# Power_System.net
KiCad netlist of a schematic drawn in Altium Designer
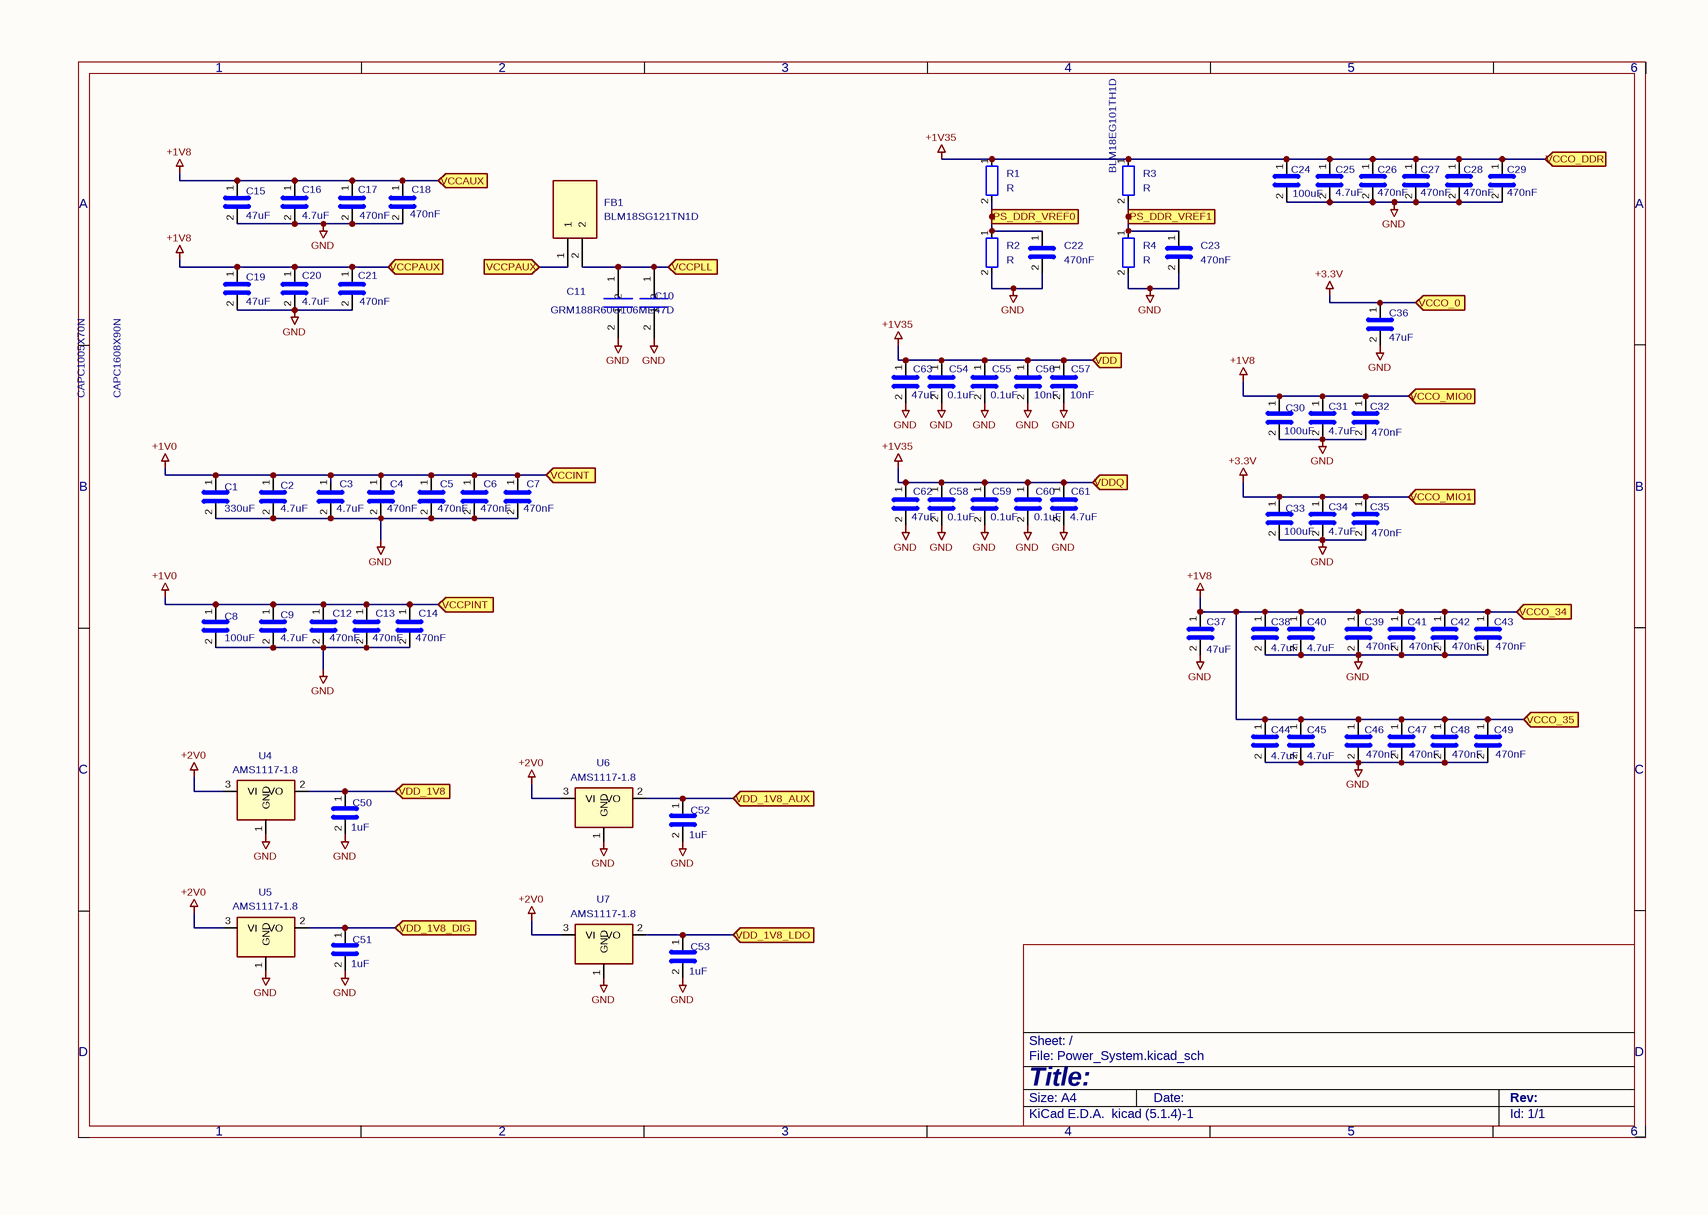
[diagram p0: Power_System.SchDoc]

(export (version "E")
  (design (tool "Eeschema 10.0.6"))
  (components
    (comp (ref "C1") (value "330uF") (libsource (lib "Device") (part "C")))
    (comp (ref "C2")
      (value "4.7uF")
      (footprint "C_0805_2012Metric_Pad1.18x1.45mm_HandSolder")
      (libsource (lib "Device") (part "C"))
    )
    (comp (ref "C3")
      (value "4.7uF")
      (footprint "C_0805_2012Metric_Pad1.18x1.45mm_HandSolder")
      (libsource (lib "Device") (part "C"))
    )
    (comp (ref "C4")
      (value "470nF")
      (footprint "C_0402_1005Metric_Pad0.74x0.62mm_HandSolder")
      (libsource (lib "Device") (part "C"))
    )
    (comp (ref "C5")
      (value "470nF")
      (footprint "C_0402_1005Metric_Pad0.74x0.62mm_HandSolder")
      (libsource (lib "Device") (part "C"))
    )
    (comp (ref "C6")
      (value "470nF")
      (footprint "C_0402_1005Metric_Pad0.74x0.62mm_HandSolder")
      (libsource (lib "Device") (part "C"))
    )
    (comp (ref "C7")
      (value "470nF")
      (footprint "C_0402_1005Metric_Pad0.74x0.62mm_HandSolder")
      (libsource (lib "Device") (part "C"))
    )
    (comp (ref "C8")
      (value "100uF")
      (footprint "C_0805_2012Metric_Pad1.18x1.45mm_HandSolder")
      (libsource (lib "Device") (part "C"))
    )
    (comp (ref "C9")
      (value "4.7uF")
      (footprint "C_0805_2012Metric_Pad1.18x1.45mm_HandSolder")
      (libsource (lib "Device") (part "C"))
    )
    (comp (ref "C10")
      (value "GRM188R60G106ME47D")
      (footprint "CAPC1608X90N")
      (libsource (lib "SamacSys") (part "GRM188R60G106ME47D"))
    )
    (comp (ref "C11")
      (value "GRM155R60J474KE19D")
      (footprint "CAPC1005X70N")
      (libsource (lib "SamacSys") (part "GRM155R60J474KE19D"))
    )
    (comp (ref "C12")
      (value "470nF")
      (footprint "C_0402_1005Metric_Pad0.74x0.62mm_HandSolder")
      (libsource (lib "Device") (part "C"))
    )
    (comp (ref "C13")
      (value "470nF")
      (footprint "C_0402_1005Metric_Pad0.74x0.62mm_HandSolder")
      (libsource (lib "Device") (part "C"))
    )
    (comp (ref "C14")
      (value "470nF")
      (footprint "C_0402_1005Metric_Pad0.74x0.62mm_HandSolder")
      (libsource (lib "Device") (part "C"))
    )
    (comp (ref "C15")
      (value "47uF")
      (footprint "C_0805_2012Metric_Pad1.18x1.45mm_HandSolder")
      (libsource (lib "Device") (part "C"))
    )
    (comp (ref "C16")
      (value "4.7uF")
      (footprint "C_0805_2012Metric_Pad1.18x1.45mm_HandSolder")
      (libsource (lib "Device") (part "C"))
    )
    (comp (ref "C17")
      (value "470nF")
      (footprint "C_0402_1005Metric_Pad0.74x0.62mm_HandSolder")
      (libsource (lib "Device") (part "C"))
    )
    (comp (ref "C18")
      (value "470nF")
      (footprint "C_0402_1005Metric_Pad0.74x0.62mm_HandSolder")
      (libsource (lib "Device") (part "C"))
    )
    (comp (ref "C19")
      (value "47uF")
      (footprint "C_0805_2012Metric_Pad1.18x1.45mm_HandSolder")
      (libsource (lib "Device") (part "C"))
    )
    (comp (ref "C20")
      (value "4.7uF")
      (footprint "C_0805_2012Metric_Pad1.18x1.45mm_HandSolder")
      (libsource (lib "Device") (part "C"))
    )
    (comp (ref "C21")
      (value "470nF")
      (footprint "C_0402_1005Metric_Pad0.74x0.62mm_HandSolder")
      (libsource (lib "Device") (part "C"))
    )
    (comp (ref "C22")
      (value "470nF")
      (footprint "C_0402_1005Metric_Pad0.74x0.62mm_HandSolder")
      (libsource (lib "Device") (part "C"))
    )
    (comp (ref "C23")
      (value "470nF")
      (footprint "C_0402_1005Metric_Pad0.74x0.62mm_HandSolder")
      (libsource (lib "Device") (part "C"))
    )
    (comp (ref "C24")
      (value "100uF")
      (footprint "C_0805_2012Metric_Pad1.18x1.45mm_HandSolder")
      (libsource (lib "Device") (part "C"))
    )
    (comp (ref "C25")
      (value "4.7uF")
      (footprint "C_0805_2012Metric_Pad1.18x1.45mm_HandSolder")
      (libsource (lib "Device") (part "C"))
    )
    (comp (ref "C26")
      (value "470nF")
      (footprint "C_0402_1005Metric_Pad0.74x0.62mm_HandSolder")
      (libsource (lib "Device") (part "C"))
    )
    (comp (ref "C27")
      (value "470nF")
      (footprint "C_0402_1005Metric_Pad0.74x0.62mm_HandSolder")
      (libsource (lib "Device") (part "C"))
    )
    (comp (ref "C28")
      (value "470nF")
      (footprint "C_0402_1005Metric_Pad0.74x0.62mm_HandSolder")
      (libsource (lib "Device") (part "C"))
    )
    (comp (ref "C29")
      (value "470nF")
      (footprint "C_0402_1005Metric_Pad0.74x0.62mm_HandSolder")
      (libsource (lib "Device") (part "C"))
    )
    (comp (ref "C30")
      (value "100uF")
      (footprint "C_0805_2012Metric_Pad1.18x1.45mm_HandSolder")
      (libsource (lib "Device") (part "C"))
    )
    (comp (ref "C31")
      (value "4.7uF")
      (footprint "C_0805_2012Metric_Pad1.18x1.45mm_HandSolder")
      (libsource (lib "Device") (part "C"))
    )
    (comp (ref "C32")
      (value "470nF")
      (footprint "C_0402_1005Metric_Pad0.74x0.62mm_HandSolder")
      (libsource (lib "Device") (part "C"))
    )
    (comp (ref "C33")
      (value "100uF")
      (footprint "C_0805_2012Metric_Pad1.18x1.45mm_HandSolder")
      (libsource (lib "Device") (part "C"))
    )
    (comp (ref "C34")
      (value "4.7uF")
      (footprint "C_0805_2012Metric_Pad1.18x1.45mm_HandSolder")
      (libsource (lib "Device") (part "C"))
    )
    (comp (ref "C35")
      (value "470nF")
      (footprint "C_0402_1005Metric_Pad0.74x0.62mm_HandSolder")
      (libsource (lib "Device") (part "C"))
    )
    (comp (ref "C36")
      (value "47uF")
      (footprint "C_0805_2012Metric_Pad1.18x1.45mm_HandSolder")
      (libsource (lib "Device") (part "C"))
    )
    (comp (ref "C37")
      (value "47uF")
      (footprint "C_0805_2012Metric_Pad1.18x1.45mm_HandSolder")
      (libsource (lib "Device") (part "C"))
    )
    (comp (ref "C38")
      (value "4.7uF")
      (footprint "C_0805_2012Metric_Pad1.18x1.45mm_HandSolder")
      (libsource (lib "Device") (part "C"))
    )
    (comp (ref "C39")
      (value "470nF")
      (footprint "C_0402_1005Metric_Pad0.74x0.62mm_HandSolder")
      (libsource (lib "Device") (part "C"))
    )
    (comp (ref "C40")
      (value "4.7uF")
      (footprint "C_0805_2012Metric_Pad1.18x1.45mm_HandSolder")
      (libsource (lib "Device") (part "C"))
    )
    (comp (ref "C41")
      (value "470nF")
      (footprint "C_0402_1005Metric_Pad0.74x0.62mm_HandSolder")
      (libsource (lib "Device") (part "C"))
    )
    (comp (ref "C42")
      (value "470nF")
      (footprint "C_0402_1005Metric_Pad0.74x0.62mm_HandSolder")
      (libsource (lib "Device") (part "C"))
    )
    (comp (ref "C43")
      (value "470nF")
      (footprint "C_0402_1005Metric_Pad0.74x0.62mm_HandSolder")
      (libsource (lib "Device") (part "C"))
    )
    (comp (ref "C44")
      (value "4.7uF")
      (footprint "C_0805_2012Metric_Pad1.18x1.45mm_HandSolder")
      (libsource (lib "Device") (part "C"))
    )
    (comp (ref "C45")
      (value "4.7uF")
      (footprint "C_0805_2012Metric_Pad1.18x1.45mm_HandSolder")
      (libsource (lib "Device") (part "C"))
    )
    (comp (ref "C46")
      (value "470nF")
      (footprint "C_0402_1005Metric_Pad0.74x0.62mm_HandSolder")
      (libsource (lib "Device") (part "C"))
    )
    (comp (ref "C47")
      (value "470nF")
      (footprint "C_0402_1005Metric_Pad0.74x0.62mm_HandSolder")
      (libsource (lib "Device") (part "C"))
    )
    (comp (ref "C48")
      (value "470nF")
      (footprint "C_0402_1005Metric_Pad0.74x0.62mm_HandSolder")
      (libsource (lib "Device") (part "C"))
    )
    (comp (ref "C49")
      (value "470nF")
      (footprint "C_0402_1005Metric_Pad0.74x0.62mm_HandSolder")
      (libsource (lib "Device") (part "C"))
    )
    (comp (ref "C50")
      (value "1uF")
      (footprint "C_0805_2012Metric_Pad1.18x1.45mm_HandSolder")
      (libsource (lib "Device") (part "C"))
    )
    (comp (ref "C51")
      (value "1uF")
      (footprint "C_0805_2012Metric_Pad1.18x1.45mm_HandSolder")
      (libsource (lib "Device") (part "C"))
    )
    (comp (ref "C52")
      (value "1uF")
      (footprint "C_0805_2012Metric_Pad1.18x1.45mm_HandSolder")
      (libsource (lib "Device") (part "C"))
    )
    (comp (ref "C53")
      (value "1uF")
      (footprint "C_0805_2012Metric_Pad1.18x1.45mm_HandSolder")
      (libsource (lib "Device") (part "C"))
    )
    (comp (ref "C54") (value "0.1uF") (footprint "C_0402_1005Metric") (libsource (lib "Device") (part "C")))
    (comp (ref "C55") (value "0.1uF") (footprint "C_0402_1005Metric") (libsource (lib "Device") (part "C")))
    (comp (ref "C56") (value "10nF") (footprint "C_0402_1005Metric") (libsource (lib "Device") (part "C")))
    (comp (ref "C57")
      (value "10nF")
      (footprint "C_0402_1005Metric_Pad0.74x0.62mm_HandSolder")
      (libsource (lib "Device") (part "C"))
    )
    (comp (ref "C58") (value "0.1uF") (footprint "C_0402_1005Metric") (libsource (lib "Device") (part "C")))
    (comp (ref "C59") (value "0.1uF") (footprint "C_0402_1005Metric") (libsource (lib "Device") (part "C")))
    (comp (ref "C60") (value "0.1uF") (footprint "C_0402_1005Metric") (libsource (lib "Device") (part "C")))
    (comp (ref "C61")
      (value "4.7uF")
      (footprint "C_0402_1005Metric_Pad0.74x0.62mm_HandSolder")
      (libsource (lib "Device") (part "C"))
    )
    (comp (ref "C62")
      (value "47uF")
      (footprint "C_0805_2012Metric_Pad1.18x1.45mm_HandSolder")
      (libsource (lib "Device") (part "C"))
    )
    (comp (ref "C63")
      (value "47uF")
      (footprint "C_0805_2012Metric_Pad1.18x1.45mm_HandSolder")
      (libsource (lib "Device") (part "C"))
    )
    (comp (ref "FB1")
      (value "BLM18SG121TN1D")
      (footprint "BLM18EG101TH1D")
      (libsource (lib "SamacSys") (part "BLM18SG121TN1D"))
    )
    (comp (ref "R1") (value "R") (libsource (lib "Device") (part "R")))
    (comp (ref "R2") (value "R") (libsource (lib "Device") (part "R")))
    (comp (ref "R3") (value "R") (libsource (lib "Device") (part "R")))
    (comp (ref "R4") (value "R") (libsource (lib "Device") (part "R")))
    (comp (ref "U4")
      (value "AMS1117-1.8")
      (footprint "SOT-223-3_TabPin2")
      (libsource (lib "Regulator_Linear") (part "AMS1117-1.8"))
    )
    (comp (ref "U5")
      (value "AMS1117-1.8")
      (footprint "SOT-223-3_TabPin2")
      (libsource (lib "Regulator_Linear") (part "AMS1117-1.8"))
    )
    (comp (ref "U6")
      (value "AMS1117-1.8")
      (footprint "SOT-223-3_TabPin2")
      (libsource (lib "Regulator_Linear") (part "AMS1117-1.8"))
    )
    (comp (ref "U7")
      (value "AMS1117-1.8")
      (footprint "SOT-223-3_TabPin2")
      (libsource (lib "Regulator_Linear") (part "AMS1117-1.8"))
    )
  )
  (nets
    (net (code "1") (name "+1V0") (class "Default")
      (node (ref "C1") (pin "1") (pinfunction "1_1") (pintype "passive"))
      (node (ref "C12") (pin "1") (pinfunction "1_1") (pintype "passive"))
      (node (ref "C13") (pin "1") (pinfunction "1_1") (pintype "passive"))
      (node (ref "C14") (pin "1") (pinfunction "1_1") (pintype "passive"))
      (node (ref "C2") (pin "1") (pinfunction "1_1") (pintype "passive"))
      (node (ref "C3") (pin "1") (pinfunction "1_1") (pintype "passive"))
      (node (ref "C4") (pin "1") (pinfunction "1_1") (pintype "passive"))
      (node (ref "C5") (pin "1") (pinfunction "1_1") (pintype "passive"))
      (node (ref "C6") (pin "1") (pinfunction "1_1") (pintype "passive"))
      (node (ref "C7") (pin "1") (pinfunction "1_1") (pintype "passive"))
      (node (ref "C8") (pin "1") (pinfunction "1_1") (pintype "passive"))
      (node (ref "C9") (pin "1") (pinfunction "1_1") (pintype "passive"))
    )
    (net (code "2") (name "+1V8") (class "Default")
      (node (ref "C15") (pin "1") (pinfunction "1_1") (pintype "passive"))
      (node (ref "C16") (pin "1") (pinfunction "1_1") (pintype "passive"))
      (node (ref "C17") (pin "1") (pinfunction "1_1") (pintype "passive"))
      (node (ref "C18") (pin "1") (pinfunction "1_1") (pintype "passive"))
      (node (ref "C19") (pin "1") (pinfunction "1_1") (pintype "passive"))
      (node (ref "C20") (pin "1") (pinfunction "1_1") (pintype "passive"))
      (node (ref "C21") (pin "1") (pinfunction "1_1") (pintype "passive"))
      (node (ref "C30") (pin "1") (pinfunction "1_1") (pintype "passive"))
      (node (ref "C31") (pin "1") (pinfunction "1_1") (pintype "passive"))
      (node (ref "C32") (pin "1") (pinfunction "1_1") (pintype "passive"))
      (node (ref "C37") (pin "1") (pinfunction "1_1") (pintype "passive"))
      (node (ref "C38") (pin "1") (pinfunction "1_1") (pintype "passive"))
      (node (ref "C39") (pin "1") (pinfunction "1_1") (pintype "passive"))
      (node (ref "C40") (pin "1") (pinfunction "1_1") (pintype "passive"))
      (node (ref "C41") (pin "1") (pinfunction "1_1") (pintype "passive"))
      (node (ref "C42") (pin "1") (pinfunction "1_1") (pintype "passive"))
      (node (ref "C43") (pin "1") (pinfunction "1_1") (pintype "passive"))
      (node (ref "C44") (pin "1") (pinfunction "1_1") (pintype "passive"))
      (node (ref "C45") (pin "1") (pinfunction "1_1") (pintype "passive"))
      (node (ref "C46") (pin "1") (pinfunction "1_1") (pintype "passive"))
      (node (ref "C47") (pin "1") (pinfunction "1_1") (pintype "passive"))
      (node (ref "C48") (pin "1") (pinfunction "1_1") (pintype "passive"))
      (node (ref "C49") (pin "1") (pinfunction "1_1") (pintype "passive"))
      (node (ref "FB1") (pin "1") (pinfunction "1_1") (pintype "passive"))
    )
    (net (code "3") (name "+1V35") (class "Default")
      (node (ref "C24") (pin "1") (pinfunction "1_1") (pintype "passive"))
      (node (ref "C25") (pin "1") (pinfunction "1_1") (pintype "passive"))
      (node (ref "C26") (pin "1") (pinfunction "1_1") (pintype "passive"))
      (node (ref "C27") (pin "1") (pinfunction "1_1") (pintype "passive"))
      (node (ref "C28") (pin "1") (pinfunction "1_1") (pintype "passive"))
      (node (ref "C29") (pin "1") (pinfunction "1_1") (pintype "passive"))
      (node (ref "C54") (pin "1") (pinfunction "1_1") (pintype "passive"))
      (node (ref "C55") (pin "1") (pinfunction "1_1") (pintype "passive"))
      (node (ref "C56") (pin "1") (pinfunction "1_1") (pintype "passive"))
      (node (ref "C57") (pin "1") (pinfunction "1_1") (pintype "passive"))
      (node (ref "C58") (pin "1") (pinfunction "1_1") (pintype "passive"))
      (node (ref "C59") (pin "1") (pinfunction "1_1") (pintype "passive"))
      (node (ref "C60") (pin "1") (pinfunction "1_1") (pintype "passive"))
      (node (ref "C61") (pin "1") (pinfunction "1_1") (pintype "passive"))
      (node (ref "C62") (pin "1") (pinfunction "1_1") (pintype "passive"))
      (node (ref "C63") (pin "1") (pinfunction "1_1") (pintype "passive"))
      (node (ref "R1") (pin "1") (pinfunction "1_1") (pintype "passive"))
      (node (ref "R3") (pin "1") (pinfunction "1_1") (pintype "passive"))
    )
    (net (code "4") (name "+2V0") (class "Default")
      (node (ref "U4") (pin "3") (pinfunction "VI_3") (pintype "passive"))
      (node (ref "U5") (pin "3") (pinfunction "VI_3") (pintype "passive"))
      (node (ref "U6") (pin "3") (pinfunction "VI_3") (pintype "passive"))
      (node (ref "U7") (pin "3") (pinfunction "VI_3") (pintype "passive"))
    )
    (net (code "5") (name "+3.3V") (class "Default")
      (node (ref "C33") (pin "1") (pinfunction "1_1") (pintype "passive"))
      (node (ref "C34") (pin "1") (pinfunction "1_1") (pintype "passive"))
      (node (ref "C35") (pin "1") (pinfunction "1_1") (pintype "passive"))
      (node (ref "C36") (pin "1") (pinfunction "1_1") (pintype "passive"))
    )
    (net (code "6") (name "/PS_DDR_VREF0") (class "Default")
      (node (ref "C22") (pin "1") (pinfunction "1_1") (pintype "passive"))
      (node (ref "R1") (pin "2") (pinfunction "2_2") (pintype "passive"))
      (node (ref "R2") (pin "1") (pinfunction "1_1") (pintype "passive"))
    )
    (net (code "7") (name "/PS_DDR_VREF1") (class "Default")
      (node (ref "C23") (pin "1") (pinfunction "1_1") (pintype "passive"))
      (node (ref "R3") (pin "2") (pinfunction "2_2") (pintype "passive"))
      (node (ref "R4") (pin "1") (pinfunction "1_1") (pintype "passive"))
    )
    (net (code "8") (name "/VCCPLL") (class "Default")
      (node (ref "C10") (pin "1") (pinfunction "1_1") (pintype "passive"))
      (node (ref "C11") (pin "1") (pinfunction "1_1") (pintype "passive"))
      (node (ref "FB1") (pin "2") (pinfunction "2_2") (pintype "passive"))
    )
    (net (code "9") (name "/VDD_1V8") (class "Default")
      (node (ref "C50") (pin "1") (pinfunction "1_1") (pintype "passive"))
      (node (ref "U4") (pin "2") (pinfunction "VO_2") (pintype "passive"))
    )
    (net (code "10") (name "/VDD_1V8_AUX") (class "Default")
      (node (ref "C52") (pin "1") (pinfunction "1_1") (pintype "passive"))
      (node (ref "U6") (pin "2") (pinfunction "VO_2") (pintype "passive"))
    )
    (net (code "11") (name "/VDD_1V8_DIG") (class "Default")
      (node (ref "C51") (pin "1") (pinfunction "1_1") (pintype "passive"))
      (node (ref "U5") (pin "2") (pinfunction "VO_2") (pintype "passive"))
    )
    (net (code "12") (name "/VDD_1V8_LDO") (class "Default")
      (node (ref "C53") (pin "1") (pinfunction "1_1") (pintype "passive"))
      (node (ref "U7") (pin "2") (pinfunction "VO_2") (pintype "passive"))
    )
    (net (code "13") (name "GND") (class "Default")
      (node (ref "C1") (pin "2") (pinfunction "2_2") (pintype "passive"))
      (node (ref "C10") (pin "2") (pinfunction "2_2") (pintype "passive"))
      (node (ref "C11") (pin "2") (pinfunction "2_2") (pintype "passive"))
      (node (ref "C12") (pin "2") (pinfunction "2_2") (pintype "passive"))
      (node (ref "C13") (pin "2") (pinfunction "2_2") (pintype "passive"))
      (node (ref "C14") (pin "2") (pinfunction "2_2") (pintype "passive"))
      (node (ref "C15") (pin "2") (pinfunction "2_2") (pintype "passive"))
      (node (ref "C16") (pin "2") (pinfunction "2_2") (pintype "passive"))
      (node (ref "C17") (pin "2") (pinfunction "2_2") (pintype "passive"))
      (node (ref "C18") (pin "2") (pinfunction "2_2") (pintype "passive"))
      (node (ref "C19") (pin "2") (pinfunction "2_2") (pintype "passive"))
      (node (ref "C2") (pin "2") (pinfunction "2_2") (pintype "passive"))
      (node (ref "C20") (pin "2") (pinfunction "2_2") (pintype "passive"))
      (node (ref "C21") (pin "2") (pinfunction "2_2") (pintype "passive"))
      (node (ref "C22") (pin "2") (pinfunction "2_2") (pintype "passive"))
      (node (ref "C23") (pin "2") (pinfunction "2_2") (pintype "passive"))
      (node (ref "C24") (pin "2") (pinfunction "2_2") (pintype "passive"))
      (node (ref "C25") (pin "2") (pinfunction "2_2") (pintype "passive"))
      (node (ref "C26") (pin "2") (pinfunction "2_2") (pintype "passive"))
      (node (ref "C27") (pin "2") (pinfunction "2_2") (pintype "passive"))
      (node (ref "C28") (pin "2") (pinfunction "2_2") (pintype "passive"))
      (node (ref "C29") (pin "2") (pinfunction "2_2") (pintype "passive"))
      (node (ref "C3") (pin "2") (pinfunction "2_2") (pintype "passive"))
      (node (ref "C30") (pin "2") (pinfunction "2_2") (pintype "passive"))
      (node (ref "C31") (pin "2") (pinfunction "2_2") (pintype "passive"))
      (node (ref "C32") (pin "2") (pinfunction "2_2") (pintype "passive"))
      (node (ref "C33") (pin "2") (pinfunction "2_2") (pintype "passive"))
      (node (ref "C34") (pin "2") (pinfunction "2_2") (pintype "passive"))
      (node (ref "C35") (pin "2") (pinfunction "2_2") (pintype "passive"))
      (node (ref "C36") (pin "2") (pinfunction "2_2") (pintype "passive"))
      (node (ref "C37") (pin "2") (pinfunction "2_2") (pintype "passive"))
      (node (ref "C38") (pin "2") (pinfunction "2_2") (pintype "passive"))
      (node (ref "C39") (pin "2") (pinfunction "2_2") (pintype "passive"))
      (node (ref "C4") (pin "2") (pinfunction "2_2") (pintype "passive"))
      (node (ref "C40") (pin "2") (pinfunction "2_2") (pintype "passive"))
      (node (ref "C41") (pin "2") (pinfunction "2_2") (pintype "passive"))
      (node (ref "C42") (pin "2") (pinfunction "2_2") (pintype "passive"))
      (node (ref "C43") (pin "2") (pinfunction "2_2") (pintype "passive"))
      (node (ref "C44") (pin "2") (pinfunction "2_2") (pintype "passive"))
      (node (ref "C45") (pin "2") (pinfunction "2_2") (pintype "passive"))
      (node (ref "C46") (pin "2") (pinfunction "2_2") (pintype "passive"))
      (node (ref "C47") (pin "2") (pinfunction "2_2") (pintype "passive"))
      (node (ref "C48") (pin "2") (pinfunction "2_2") (pintype "passive"))
      (node (ref "C49") (pin "2") (pinfunction "2_2") (pintype "passive"))
      (node (ref "C5") (pin "2") (pinfunction "2_2") (pintype "passive"))
      (node (ref "C50") (pin "2") (pinfunction "2_2") (pintype "passive"))
      (node (ref "C51") (pin "2") (pinfunction "2_2") (pintype "passive"))
      (node (ref "C52") (pin "2") (pinfunction "2_2") (pintype "passive"))
      (node (ref "C53") (pin "2") (pinfunction "2_2") (pintype "passive"))
      (node (ref "C54") (pin "2") (pinfunction "2_2") (pintype "passive"))
      (node (ref "C55") (pin "2") (pinfunction "2_2") (pintype "passive"))
      (node (ref "C56") (pin "2") (pinfunction "2_2") (pintype "passive"))
      (node (ref "C57") (pin "2") (pinfunction "2_2") (pintype "passive"))
      (node (ref "C58") (pin "2") (pinfunction "2_2") (pintype "passive"))
      (node (ref "C59") (pin "2") (pinfunction "2_2") (pintype "passive"))
      (node (ref "C6") (pin "2") (pinfunction "2_2") (pintype "passive"))
      (node (ref "C60") (pin "2") (pinfunction "2_2") (pintype "passive"))
      (node (ref "C61") (pin "2") (pinfunction "2_2") (pintype "passive"))
      (node (ref "C62") (pin "2") (pinfunction "2_2") (pintype "passive"))
      (node (ref "C63") (pin "2") (pinfunction "2_2") (pintype "passive"))
      (node (ref "C7") (pin "2") (pinfunction "2_2") (pintype "passive"))
      (node (ref "C8") (pin "2") (pinfunction "2_2") (pintype "passive"))
      (node (ref "C9") (pin "2") (pinfunction "2_2") (pintype "passive"))
      (node (ref "R2") (pin "2") (pinfunction "2_2") (pintype "passive"))
      (node (ref "R4") (pin "2") (pinfunction "2_2") (pintype "passive"))
      (node (ref "U4") (pin "1") (pinfunction "GND_1") (pintype "passive"))
      (node (ref "U5") (pin "1") (pinfunction "GND_1") (pintype "passive"))
      (node (ref "U6") (pin "1") (pinfunction "GND_1") (pintype "passive"))
      (node (ref "U7") (pin "1") (pinfunction "GND_1") (pintype "passive"))
    )
  )
)
